# Linear_Actuator_V3_1_SchDoc.net
KiCad netlist of a schematic drawn in Altium Designer
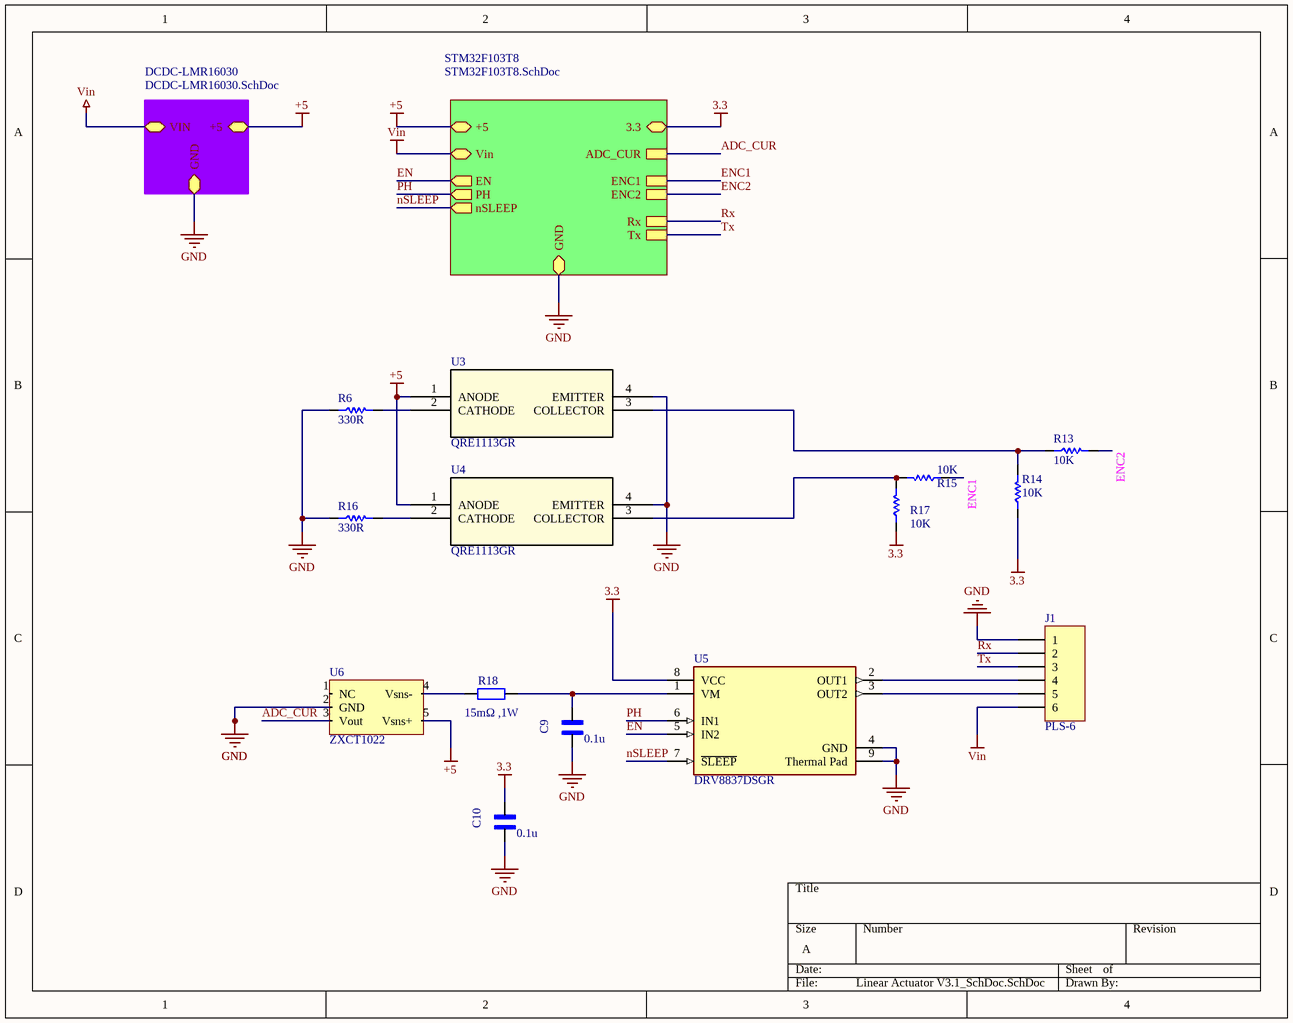
[diagram p0: Linear Actuator V3.1_SchDoc.SchDoc]

(export (version "E")
  (design (tool "Eeschema 10.0.6"))
  (components
    (comp (ref "C9")
      (value "0.1u")
      (footprint "*CAPC1608X90")
      (description "Cap Thin Film 0.1uf 50v 0603")
      (fields (field (name "MF") "AVX") (field (name "MP") "GX035C104MAT2-500 or CL10B104JB8NNNC"))
      (libsource (lib "lib") (part "GX035C104MAT2-500"))
    )
    (comp (ref "C10")
      (value "0.1u")
      (footprint "*CAPC1608X90")
      (description "Cap Thin Film 0.1uf 50v 0603")
      (fields (field (name "MF") "AVX") (field (name "MP") "GX035C104MAT2-500 or CL10B104JB8NNNC"))
      (libsource (lib "lib") (part "GX035C104MAT2-500"))
    )
    (comp (ref "J1")
      (value "PLS-6")
      (footprint "HDR Side 6 pin")
      (description "PLS-6 (DS1021-1x6), Вилка штыревая 2.54мм 1x6 прямая тип1")
      (libsource (lib "lib") (part "PLS-6"))
    )
    (comp (ref "R6")
      (value "330R")
      (footprint "RES 0603 (1608X06L)")
      (description "Resistor")
      (fields (field (name "TOLERANCE") "5%") (field (name "POWER") "1/8 W"))
      (libsource (lib "R2T Team Library") (part "Resistor"))
    )
    (comp (ref "R13")
      (value "10K")
      (footprint "RES 0603 (1608X06L)")
      (description "Resistor")
      (fields (field (name "TOLERANCE") "5%") (field (name "POWER") "1/8 W"))
      (libsource (lib "R2T Team Library") (part "Resistor"))
    )
    (comp (ref "R14")
      (value "10K")
      (footprint "RES 0603 (1608X06L)")
      (description "Resistor")
      (fields (field (name "TOLERANCE") "5%") (field (name "POWER") "1/8 W"))
      (libsource (lib "R2T Team Library") (part "Resistor"))
    )
    (comp (ref "R15")
      (value "10K")
      (footprint "RES 0603 (1608X06L)")
      (description "Resistor")
      (fields (field (name "TOLERANCE") "5%") (field (name "POWER") "1/8 W"))
      (libsource (lib "R2T Team Library") (part "Resistor"))
    )
    (comp (ref "R16")
      (value "330R")
      (footprint "RES 0603 (1608X06L)")
      (description "Resistor")
      (fields (field (name "TOLERANCE") "5%") (field (name "POWER") "1/8 W"))
      (libsource (lib "R2T Team Library") (part "Resistor"))
    )
    (comp (ref "R17")
      (value "10K")
      (footprint "RES 0603 (1608X06L)")
      (description "Resistor")
      (fields (field (name "TOLERANCE") "5%") (field (name "POWER") "1/8 W"))
      (libsource (lib "R2T Team Library") (part "Resistor"))
    )
    (comp (ref "R18")
      (value "15mΩ ,1W")
      (footprint "RES2512")
      (description "Resistor")
      (fields (field (name "Comment") "resistor") (field (name "PUBLISHER") "Altium Limited"))
      (libsource (lib "lib") (part "resistor"))
    )
    (comp (ref "U3")
      (value "QRE1113GR")
      (footprint "SMD4_2P90X3P60_ONS")
      (description "No Description Available")
      (fields (field (name "COPYRIGHT") "Copyright (C) 2018 Accelerated Designs. All rights reserved"))
      (libsource (lib "lib") (part "QRE1113GR"))
    )
    (comp (ref "U4")
      (value "QRE1113GR")
      (footprint "SMD4_2P90X3P60_ONS")
      (description "No Description Available")
      (fields (field (name "COPYRIGHT") "Copyright (C) 2018 Accelerated Designs. All rights reserved"))
      (libsource (lib "lib") (part "QRE1113GR"))
    )
    (comp (ref "U5")
      (value "DRV8837DSGR")
      (footprint "FP-DSG0008A-MFG")
      (description "IC MOTOR DRIVER PAR 8WSON")
      (fields
        (field (name "MANUFACTURER") "Texas Instruments")
        (field (name "OCTOPART") "https://octopart.com/drv8837dsgr-texas+instruments-23786726")
      )
      (libsource (lib "Altium Content Vault") (part "0edabe62f55b79d65ef7cb8a22a7164"))
    )
    (comp (ref "U6") (value "ZXCT1022") (footprint "SOT23-5") (libsource (lib "lib") (part "ZXCT1022")))
  )
  (nets
    (net (code "1") (name "+5") (class "Default")
      (node (ref "U3") (pin "1") (pinfunction "ANODE_1") (pintype "passive"))
      (node (ref "U4") (pin "1") (pinfunction "ANODE_1") (pintype "passive"))
      (node (ref "U6") (pin "5") (pinfunction "Vsns+_5") (pintype "passive"))
    )
    (net (code "2") (name "/ADC_CUR") (class "Default")
      (node (ref "U6") (pin "3") (pinfunction "Vout_3") (pintype "passive"))
    )
    (net (code "3") (name "/EN") (class "Default")
      (node (ref "U5") (pin "5") (pinfunction "IN2_5") (pintype "input"))
    )
    (net (code "4") (name "/ENC1") (class "Default")
      (node (ref "R15") (pin "1") (pinfunction "1_1") (pintype "passive"))
    )
    (net (code "5") (name "/ENC2") (class "Default")
      (node (ref "R13") (pin "2") (pinfunction "2_2") (pintype "passive"))
    )
    (net (code "6") (name "/PH") (class "Default")
      (node (ref "U5") (pin "6") (pinfunction "IN1_6") (pintype "input"))
    )
    (net (code "7") (name "/Rx") (class "Default")
      (node (ref "J1") (pin "2") (pinfunction "2_2") (pintype "passive"))
    )
    (net (code "8") (name "/Tx") (class "Default")
      (node (ref "J1") (pin "3") (pinfunction "3_3") (pintype "passive"))
    )
    (net (code "9") (name "/nSLEEP") (class "Default")
      (node (ref "U5") (pin "7") (pinfunction "~{SLEEP}_7") (pintype "input"))
    )
    (net (code "10") (name "3.3") (class "Default")
      (node (ref "C10") (pin "1") (pinfunction "1_1") (pintype "passive"))
      (node (ref "R14") (pin "1") (pinfunction "1_1") (pintype "passive"))
      (node (ref "R17") (pin "1") (pinfunction "1_1") (pintype "passive"))
      (node (ref "U5") (pin "8") (pinfunction "VCC_8") (pintype "power_in"))
    )
    (net (code "11") (name "GND") (class "Default")
      (node (ref "C10") (pin "2") (pinfunction "2_2") (pintype "passive"))
      (node (ref "C9") (pin "2") (pinfunction "2_2") (pintype "passive"))
      (node (ref "J1") (pin "1") (pinfunction "1_1") (pintype "passive"))
      (node (ref "R16") (pin "1") (pinfunction "1_1") (pintype "passive"))
      (node (ref "R6") (pin "1") (pinfunction "1_1") (pintype "passive"))
      (node (ref "U3") (pin "4") (pinfunction "EMITTER_4") (pintype "passive"))
      (node (ref "U4") (pin "4") (pinfunction "EMITTER_4") (pintype "passive"))
      (node (ref "U5") (pin "4") (pinfunction "GND_4") (pintype "power_in"))
      (node (ref "U5") (pin "9") (pinfunction "Thermal_Pad_9") (pintype "power_in"))
      (node (ref "U6") (pin "2") (pinfunction "GND_2") (pintype "passive"))
    )
    (net (code "12") (name "Net-(U3-CATHODE)") (class "Default")
      (node (ref "R6") (pin "2") (pinfunction "2_2") (pintype "passive"))
      (node (ref "U3") (pin "2") (pinfunction "CATHODE_2") (pintype "passive"))
    )
    (net (code "13") (name "Net-(U3-COLLECTOR)") (class "Default")
      (node (ref "R13") (pin "1") (pinfunction "1_1") (pintype "passive"))
      (node (ref "R14") (pin "2") (pinfunction "2_2") (pintype "passive"))
      (node (ref "U3") (pin "3") (pinfunction "COLLECTOR_3") (pintype "passive"))
    )
    (net (code "14") (name "Net-(U4-CATHODE)") (class "Default")
      (node (ref "R16") (pin "2") (pinfunction "2_2") (pintype "passive"))
      (node (ref "U4") (pin "2") (pinfunction "CATHODE_2") (pintype "passive"))
    )
    (net (code "15") (name "Net-(U4-COLLECTOR)") (class "Default")
      (node (ref "R15") (pin "2") (pinfunction "2_2") (pintype "passive"))
      (node (ref "R17") (pin "2") (pinfunction "2_2") (pintype "passive"))
      (node (ref "U4") (pin "3") (pinfunction "COLLECTOR_3") (pintype "passive"))
    )
    (net (code "16") (name "Net-(U5-OUT1)") (class "Default")
      (node (ref "J1") (pin "4") (pinfunction "4_4") (pintype "passive"))
      (node (ref "U5") (pin "2") (pinfunction "OUT1_2") (pintype "output"))
    )
    (net (code "17") (name "Net-(U5-OUT2)") (class "Default")
      (node (ref "J1") (pin "5") (pinfunction "5_5") (pintype "passive"))
      (node (ref "U5") (pin "3") (pinfunction "OUT2_3") (pintype "output"))
    )
    (net (code "18") (name "Net-(U5-VM)") (class "Default")
      (node (ref "C9") (pin "1") (pinfunction "1_1") (pintype "passive"))
      (node (ref "R18") (pin "2") (pinfunction "2_2") (pintype "passive"))
      (node (ref "U5") (pin "1") (pinfunction "VM_1") (pintype "power_in"))
    )
    (net (code "19") (name "Net-(U6-Vsns-)") (class "Default")
      (node (ref "R18") (pin "1") (pinfunction "1_1") (pintype "passive"))
      (node (ref "U6") (pin "4") (pinfunction "Vsns-_4") (pintype "passive"))
    )
    (net (code "20") (name "Vin") (class "Default")
      (node (ref "J1") (pin "6") (pinfunction "6_6") (pintype "passive"))
    )
    (net (code "21") (name "unconnected-(U6-NC-Pad1)") (class "Default")
      (node (ref "U6") (pin "1") (pinfunction "NC_1") (pintype "passive"))
    )
  )
)
